# power_supply.net
KiCad netlist of a schematic drawn in Altium Designer
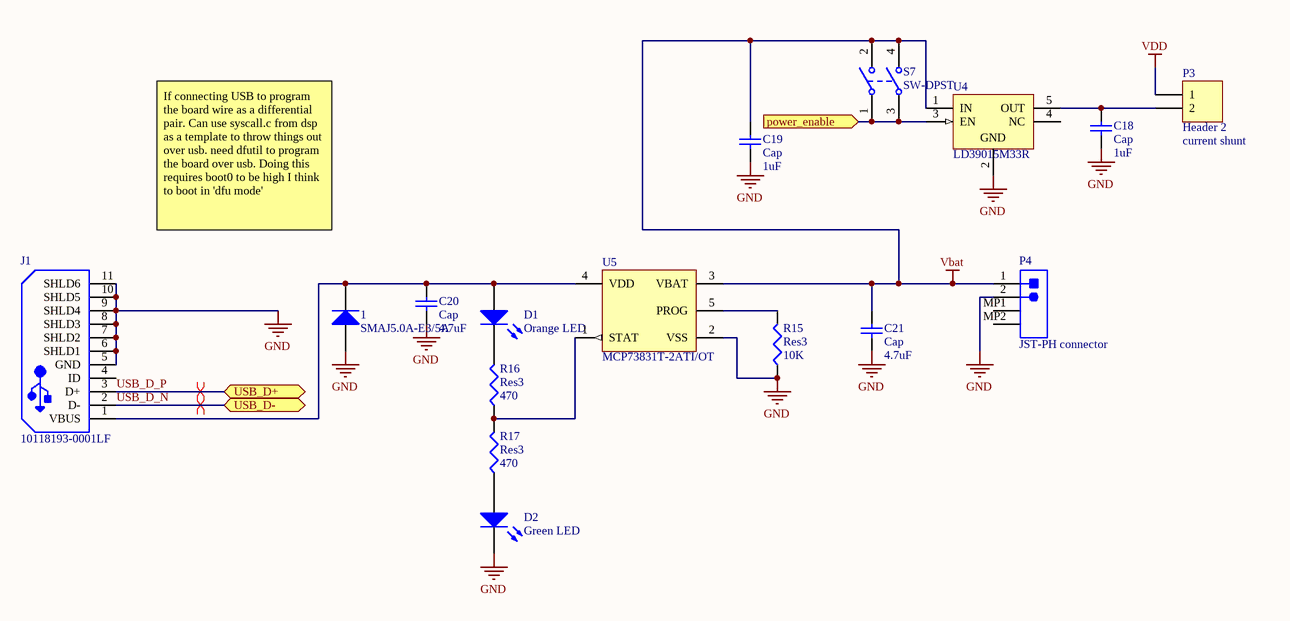
[diagram p0: power_supply.SchDoc]

(export (version "E")
  (design (tool "Eeschema 10.0.6"))
  (components
    (comp (ref "1")
      (value "SMAJ5.0A-E3/5A")
      (footprint "VISH-DO-214AC-2_N")
      (fields (field (name "MANUFACTURER") "Vishay Semiconductor"))
      (libsource (lib "Altium Content Vault") (part "VISH-K1A2-2"))
    )
    (comp (ref "C18")
      (value "Cap")
      (footprint "C0805")
      (description "Capacitor")
      (fields (field (name "ALTIUM_VALUE") "1uF") (field (name "PUBLISHER") "Altium Limited"))
      (libsource (lib "Miscellaneous Devices") (part "Cap"))
    )
    (comp (ref "C19")
      (value "Cap")
      (footprint "C0805")
      (description "Capacitor")
      (fields (field (name "ALTIUM_VALUE") "1uF") (field (name "PUBLISHER") "Altium Limited"))
      (libsource (lib "Miscellaneous Devices") (part "Cap"))
    )
    (comp (ref "C20")
      (value "Cap")
      (footprint "C0805")
      (description "Capacitor")
      (fields (field (name "ALTIUM_VALUE") "4.7uF") (field (name "PUBLISHER") "Altium Limited"))
      (libsource (lib "Miscellaneous Devices") (part "Cap"))
    )
    (comp (ref "C21")
      (value "Cap")
      (footprint "C0805")
      (description "Capacitor")
      (fields (field (name "ALTIUM_VALUE") "4.7uF") (field (name "PUBLISHER") "Altium Limited"))
      (libsource (lib "Miscellaneous Devices") (part "Cap"))
    )
    (comp (ref "D1")
      (value "Orange LED")
      (footprint "3.2X1.6X1.1")
      (description "Typical RED, GREEN, YELLOW, AMBER GaAs LED")
      (fields (field (name "PUBLISHER") "Altium Limited"))
      (libsource (lib "Miscellaneous Devices") (part "LED2"))
    )
    (comp (ref "D2")
      (value "Green LED")
      (footprint "3.2X1.6X1.1")
      (description "Typical RED, GREEN, YELLOW, AMBER GaAs LED")
      (fields (field (name "PUBLISHER") "Altium Limited"))
      (libsource (lib "Miscellaneous Devices") (part "LED2"))
    )
    (comp (ref "J1")
      (value "10118193-0001LF")
      (footprint "FCI-10118193-0001LF-5_V")
      (description "Micro USB B Type Receptacle, -55 to 85 degC, 5-Pin SMD, RoHS, Tape and Reel")
      (fields (field (name "MANUFACTURER") "FCI"))
      (libsource (lib "Altium Content Vault") (part "USB-5-6SHLD"))
    )
    (comp (ref "P3")
      (value "Header 2")
      (footprint "HDR1X2")
      (description "Header, 2-Pin")
      (fields (field (name "PUBLISHER") "Altium Limited"))
      (libsource (lib "Miscellaneous Connectors") (part "Header 2"))
    )
    (comp (ref "P4")
      (value "JST-PH connector")
      (footprint "JST- S2B-PH-SM4-TB(LF)(SN)-2_V")
      (description "Male Header, Pitch 2 mm, 1 x 2 Position, Height 5.5 mm, -25 to 85 degC, RoHS, Tape and Reel")
      (libsource (lib "Altium Content Vault") (part "CN-1P-2M-R2"))
    )
    (comp (ref "R15")
      (value "Res3")
      (footprint "1608[0603]")
      (description "Resistor")
      (fields (field (name "ALTIUM_VALUE") "10K") (field (name "PUBLISHER") "Altium Limited"))
      (libsource (lib "Miscellaneous Devices") (part "Res3"))
    )
    (comp (ref "R16")
      (value "Res3")
      (footprint "1608[0603]")
      (description "Resistor")
      (fields (field (name "ALTIUM_VALUE") "470") (field (name "PUBLISHER") "Altium Limited"))
      (libsource (lib "Miscellaneous Devices") (part "Res3"))
    )
    (comp (ref "R17")
      (value "Res3")
      (footprint "1608[0603]")
      (description "Resistor")
      (fields (field (name "ALTIUM_VALUE") "470") (field (name "PUBLISHER") "Altium Limited"))
      (libsource (lib "Miscellaneous Devices") (part "Res3"))
    )
    (comp (ref "S7")
      (value "SW-DPST")
      (footprint "PCBComponent_1")
      (description "Double-Pole, Single-Throw Switch")
      (fields (field (name "PUBLISHER") "Altium Limited"))
      (libsource (lib "Miscellaneous Devices") (part "SW-DPST"))
    )
    (comp (ref "U4")
      (value "LD39015M33R")
      (footprint "SOT23-5L_N")
      (description "150 mA Low Quiescent Current Low Noise Voltage Regulator, 3.3V, 5-Pin SOT-23, Tape and Reel")
      (libsource (lib "Altium Content Vault") (part "PM-REG-LD39015M-SOT5"))
    )
    (comp (ref "U5")
      (value "MCP73831T-2ATI/OT")
      (footprint "SOT-23-OT5_N")
      (libsource (lib "Altium Content Vault") (part "PM-BM-MCP73831-SOT5"))
    )
  )
  (nets
    (net (code "1") (name "/USB_D_N") (class "Default")
      (node (ref "J1") (pin "2") (pinfunction "D-_2") (pintype "passive"))
    )
    (net (code "2") (name "/USB_D_P") (class "Default")
      (node (ref "J1") (pin "3") (pinfunction "D+_3") (pintype "passive"))
    )
    (net (code "3") (name "/power_enable") (class "Default")
      (node (ref "S7") (pin "1") (pinfunction "COMMON1_1") (pintype "passive"))
      (node (ref "S7") (pin "3") (pinfunction "COMMON2_3") (pintype "passive"))
      (node (ref "U4") (pin "3") (pinfunction "EN_3") (pintype "input"))
    )
    (net (code "4") (name "GND") (class "Default")
      (node (ref "1") (pin "2") (pinfunction "A_2") (pintype "passive"))
      (node (ref "C18") (pin "1") (pinfunction "1_1") (pintype "passive"))
      (node (ref "C19") (pin "1") (pinfunction "1_1") (pintype "passive"))
      (node (ref "C20") (pin "1") (pinfunction "1_1") (pintype "passive"))
      (node (ref "C21") (pin "1") (pinfunction "1_1") (pintype "passive"))
      (node (ref "D2") (pin "2") (pinfunction "K_2") (pintype "passive"))
      (node (ref "J1") (pin "10") (pinfunction "SHLD5_10") (pintype "passive"))
      (node (ref "J1") (pin "11") (pinfunction "SHLD6_11") (pintype "passive"))
      (node (ref "J1") (pin "5") (pinfunction "GND_5") (pintype "passive"))
      (node (ref "J1") (pin "6") (pinfunction "SHLD1_6") (pintype "passive"))
      (node (ref "J1") (pin "7") (pinfunction "SHLD2_7") (pintype "passive"))
      (node (ref "J1") (pin "8") (pinfunction "SHLD3_8") (pintype "passive"))
      (node (ref "J1") (pin "9") (pinfunction "SHLD4_9") (pintype "passive"))
      (node (ref "P4") (pin "2") (pinfunction "2_2") (pintype "passive"))
      (node (ref "R15") (pin "1") (pinfunction "1_1") (pintype "passive"))
      (node (ref "U4") (pin "2") (pinfunction "GND_2") (pintype "power_in"))
      (node (ref "U5") (pin "2") (pinfunction "VSS_2") (pintype "power_in"))
    )
    (net (code "5") (name "Net-(1-K)") (class "Default")
      (node (ref "1") (pin "1") (pinfunction "K_1") (pintype "passive"))
      (node (ref "C20") (pin "2") (pinfunction "2_2") (pintype "passive"))
      (node (ref "D1") (pin "1") (pinfunction "A_1") (pintype "passive"))
      (node (ref "J1") (pin "1") (pinfunction "VBUS_1") (pintype "passive"))
      (node (ref "U5") (pin "4") (pinfunction "VDD_4") (pintype "power_in"))
    )
    (net (code "6") (name "Net-(D1-K)") (class "Default")
      (node (ref "D1") (pin "2") (pinfunction "K_2") (pintype "passive"))
      (node (ref "R16") (pin "2") (pinfunction "2_2") (pintype "passive"))
    )
    (net (code "7") (name "Net-(D2-A)") (class "Default")
      (node (ref "D2") (pin "1") (pinfunction "A_1") (pintype "passive"))
      (node (ref "R17") (pin "1") (pinfunction "1_1") (pintype "passive"))
    )
    (net (code "8") (name "Net-(U4-OUT)") (class "Default")
      (node (ref "C18") (pin "2") (pinfunction "2_2") (pintype "passive"))
      (node (ref "P3") (pin "2") (pinfunction "2_2") (pintype "passive"))
      (node (ref "U4") (pin "5") (pinfunction "OUT_5") (pintype "power_in"))
    )
    (net (code "9") (name "Net-(U5-PROG)") (class "Default")
      (node (ref "R15") (pin "2") (pinfunction "2_2") (pintype "passive"))
      (node (ref "U5") (pin "5") (pinfunction "PROG_5") (pintype "passive"))
    )
    (net (code "10") (name "Net-(U5-STAT)") (class "Default")
      (node (ref "R16") (pin "1") (pinfunction "1_1") (pintype "passive"))
      (node (ref "R17") (pin "2") (pinfunction "2_2") (pintype "passive"))
      (node (ref "U5") (pin "1") (pinfunction "STAT_1") (pintype "output"))
    )
    (net (code "11") (name "VDD") (class "Default")
      (node (ref "P3") (pin "1") (pinfunction "1_1") (pintype "passive"))
    )
    (net (code "12") (name "Vbat") (class "Default")
      (node (ref "C19") (pin "2") (pinfunction "2_2") (pintype "passive"))
      (node (ref "C21") (pin "2") (pinfunction "2_2") (pintype "passive"))
      (node (ref "P4") (pin "1") (pinfunction "1_1") (pintype "passive"))
      (node (ref "S7") (pin "2") (pinfunction "NO1_2") (pintype "passive"))
      (node (ref "S7") (pin "4") (pinfunction "NO2_4") (pintype "passive"))
      (node (ref "U4") (pin "1") (pinfunction "IN_1") (pintype "power_in"))
      (node (ref "U5") (pin "3") (pinfunction "VBAT_3") (pintype "power_in"))
    )
    (net (code "13") (name "unconnected-(J1-ID-Pad4)") (class "Default")
      (node (ref "J1") (pin "4") (pinfunction "ID_4") (pintype "passive"))
    )
    (net (code "14") (name "unconnected-(P4-PadMP1)") (class "Default")
      (node (ref "P4") (pin "MP1") (pinfunction "MP1_MP1") (pintype "passive"))
    )
    (net (code "15") (name "unconnected-(P4-PadMP2)") (class "Default")
      (node (ref "P4") (pin "MP2") (pinfunction "MP2_MP2") (pintype "passive"))
    )
    (net (code "16") (name "unconnected-(U4-NC-Pad4)") (class "Default")
      (node (ref "U4") (pin "4") (pinfunction "NC_4") (pintype "passive"))
    )
  )
)
